# 03_SDCard.net
KiCad netlist of a schematic drawn in Altium Designer
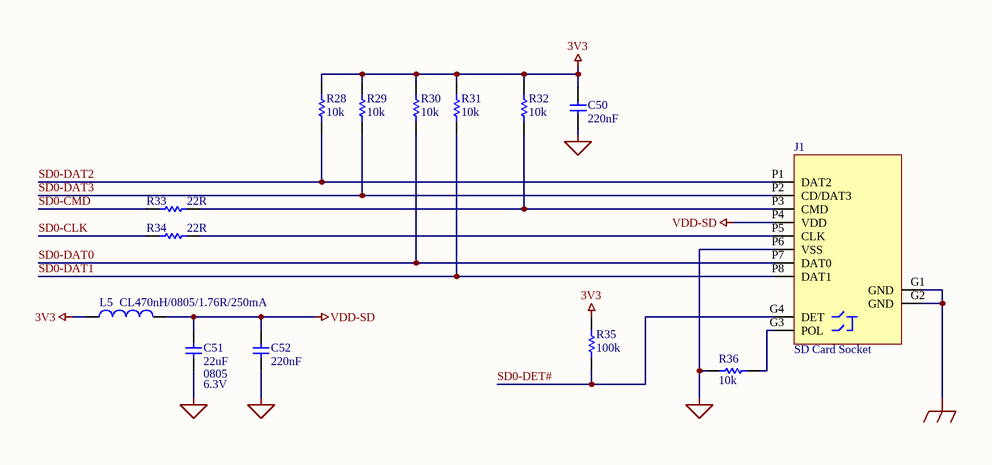
[diagram p0: [03]SDCard.SchDoc]

(export (version "E")
  (design (tool "Eeschema 10.0.6"))
  (components
    (comp (ref "C50")
      (value "220nF")
      (footprint "C0402")
      (description "SMD Capacitor")
      (fields (field (name "MPN") "?") (field (name "TOLERANCE") "20%"))
      (libsource (lib "local") (part "CAP"))
    )
    (comp (ref "C51")
      (value "22uF")
      (footprint "C0805")
      (description "SMD Capacitor")
      (fields
        (field (name "MPN") "?")
        (field (name "TOLERANCE") "20%")
        (field (name "VOLTAGE") "6.3V")
        (field (name "PACKAGE / CASE") "0805")
      )
      (libsource (lib "local") (part "CAP"))
    )
    (comp (ref "C52")
      (value "220nF")
      (footprint "C0402")
      (description "SMD Capacitor")
      (fields (field (name "MPN") "?") (field (name "TOLERANCE") "20%"))
      (libsource (lib "local") (part "CAP"))
    )
    (comp (ref "J1")
      (value "SD Card Socket")
      (description "SMD SD Card Socket")
      (fields (field (name "MPN") "502570-0893") (field (name "MANUFACTURER") "Molex"))
      (libsource (lib "local") (part "SD/MMC"))
    )
    (comp (ref "L5")
      (value "CL470nH/0805/1.76R/250mA")
      (description "SMD Coil")
      (fields (field (name "MPN") "?") (field (name "Comment") "SMD Coil Chip"))
      (libsource (lib "local") (part "COIL"))
    )
    (comp (ref "R28")
      (value "10k")
      (description "SMD Resistor")
      (fields (field (name "MPN") "?") (field (name "TOLERANCE") "1%"))
      (libsource (lib "local") (part "RES"))
    )
    (comp (ref "R29")
      (value "10k")
      (description "SMD Resistor")
      (fields (field (name "MPN") "?") (field (name "TOLERANCE") "1%"))
      (libsource (lib "local") (part "RES"))
    )
    (comp (ref "R30")
      (value "10k")
      (description "SMD Resistor")
      (fields (field (name "MPN") "?") (field (name "TOLERANCE") "1%"))
      (libsource (lib "local") (part "RES"))
    )
    (comp (ref "R31")
      (value "10k")
      (description "SMD Resistor")
      (fields (field (name "MPN") "?") (field (name "TOLERANCE") "1%"))
      (libsource (lib "local") (part "RES"))
    )
    (comp (ref "R32")
      (value "10k")
      (description "SMD Resistor")
      (fields (field (name "MPN") "?") (field (name "TOLERANCE") "1%"))
      (libsource (lib "local") (part "RES"))
    )
    (comp (ref "R33")
      (value "22R")
      (description "SMD Resistor")
      (fields (field (name "MPN") "?") (field (name "TOLERANCE") "1%"))
      (libsource (lib "local") (part "RES"))
    )
    (comp (ref "R34")
      (value "22R")
      (description "SMD Resistor")
      (fields (field (name "MPN") "?") (field (name "TOLERANCE") "1%"))
      (libsource (lib "local") (part "RES"))
    )
    (comp (ref "R35")
      (value "100k")
      (description "SMD Resistor")
      (fields (field (name "MPN") "?") (field (name "TOLERANCE") "1%"))
      (libsource (lib "local") (part "RES"))
    )
    (comp (ref "R36")
      (value "10k")
      (description "SMD Resistor")
      (fields (field (name "MPN") "?") (field (name "TOLERANCE") "1%"))
      (libsource (lib "local") (part "RES"))
    )
  )
  (nets
    (net (code "1") (name "/SD0-CLK") (class "Default")
      (node (ref "R34") (pin "1") (pinfunction "1_1") (pintype "passive"))
    )
    (net (code "2") (name "/SD0-CMD") (class "Default")
      (node (ref "R33") (pin "1") (pinfunction "1_1") (pintype "passive"))
    )
    (net (code "3") (name "/SD0-DAT0") (class "Default")
      (node (ref "J1") (pin "P7") (pinfunction "DAT0_P7") (pintype "passive"))
      (node (ref "R30") (pin "2") (pinfunction "2_2") (pintype "passive"))
    )
    (net (code "4") (name "/SD0-DAT1") (class "Default")
      (node (ref "J1") (pin "P8") (pinfunction "DAT1_P8") (pintype "passive"))
      (node (ref "R31") (pin "2") (pinfunction "2_2") (pintype "passive"))
    )
    (net (code "5") (name "/SD0-DAT2") (class "Default")
      (node (ref "J1") (pin "P1") (pinfunction "DAT2_P1") (pintype "passive"))
      (node (ref "R28") (pin "2") (pinfunction "2_2") (pintype "passive"))
    )
    (net (code "6") (name "/SD0-DAT3") (class "Default")
      (node (ref "J1") (pin "P2") (pinfunction "CD/DAT3_P2") (pintype "passive"))
      (node (ref "R29") (pin "2") (pinfunction "2_2") (pintype "passive"))
    )
    (net (code "7") (name "/SD0-DET#") (class "Default")
      (node (ref "J1") (pin "G4") (pinfunction "DET_G4") (pintype "passive"))
      (node (ref "R35") (pin "2") (pinfunction "2_2") (pintype "passive"))
    )
    (net (code "8") (name "3V3") (class "Default")
      (node (ref "C50") (pin "2") (pinfunction "2_2") (pintype "passive"))
      (node (ref "L5") (pin "1") (pinfunction "1_1") (pintype "passive"))
      (node (ref "R28") (pin "1") (pinfunction "1_1") (pintype "passive"))
      (node (ref "R29") (pin "1") (pinfunction "1_1") (pintype "passive"))
      (node (ref "R30") (pin "1") (pinfunction "1_1") (pintype "passive"))
      (node (ref "R31") (pin "1") (pinfunction "1_1") (pintype "passive"))
      (node (ref "R32") (pin "1") (pinfunction "1_1") (pintype "passive"))
      (node (ref "R35") (pin "1") (pinfunction "1_1") (pintype "passive"))
    )
    (net (code "9") (name "Net-(J1-CLK)") (class "Default")
      (node (ref "J1") (pin "P5") (pinfunction "CLK_P5") (pintype "passive"))
      (node (ref "R34") (pin "2") (pinfunction "2_2") (pintype "passive"))
    )
    (net (code "10") (name "Net-(J1-CMD)") (class "Default")
      (node (ref "J1") (pin "P3") (pinfunction "CMD_P3") (pintype "passive"))
      (node (ref "R32") (pin "2") (pinfunction "2_2") (pintype "passive"))
      (node (ref "R33") (pin "2") (pinfunction "2_2") (pintype "passive"))
    )
    (net (code "11") (name "Net-(J1-POL)") (class "Default")
      (node (ref "J1") (pin "G3") (pinfunction "POL_G3") (pintype "passive"))
      (node (ref "R36") (pin "2") (pinfunction "2_2") (pintype "passive"))
    )
    (net (code "12") (name "SGND") (class "Default")
      (node (ref "C50") (pin "1") (pinfunction "1_1") (pintype "passive"))
      (node (ref "C51") (pin "2") (pinfunction "2_2") (pintype "passive"))
      (node (ref "C52") (pin "1") (pinfunction "1_1") (pintype "passive"))
      (node (ref "J1") (pin "G1") (pinfunction "GND_G1") (pintype "passive"))
      (node (ref "J1") (pin "G2") (pinfunction "GND_G2") (pintype "passive"))
      (node (ref "J1") (pin "P6") (pinfunction "VSS_P6") (pintype "passive"))
      (node (ref "R36") (pin "1") (pinfunction "1_1") (pintype "passive"))
    )
    (net (code "13") (name "VDD-SD") (class "Default")
      (node (ref "C51") (pin "1") (pinfunction "1_1") (pintype "passive"))
      (node (ref "C52") (pin "2") (pinfunction "2_2") (pintype "passive"))
      (node (ref "J1") (pin "P4") (pinfunction "VDD_P4") (pintype "passive"))
      (node (ref "L5") (pin "2") (pinfunction "2_2") (pintype "passive"))
    )
  )
)
